# Reefing-Telemetry.net
KiCad netlist of a schematic drawn in Altium Designer
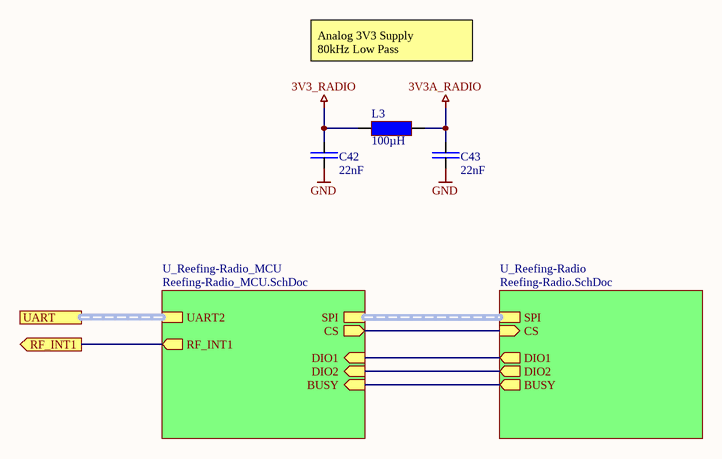
[diagram p0: Reefing-Telemetry.SchDoc]

(export (version "E")
  (design (tool "Eeschema 10.0.6"))
  (components
    (comp (ref "C42")
      (value "22nF")
      (footprint "SMD Keramikkondensator 0805")
      (description "SMD Ceramic Capacitor E6")
      (libsource (lib "Ceramic Capacitors-E6") (part "E6 - 22nF"))
    )
    (comp (ref "C43")
      (value "22nF")
      (footprint "SMD Keramikkondensator 0805")
      (description "SMD Ceramic Capacitor E6")
      (libsource (lib "Ceramic Capacitors-E6") (part "E6 - 22nF"))
    )
    (comp (ref "L3")
      (value "100µH")
      (footprint "SMD Inductor 1812")
      (description "0.25A 100µH ±20% 144mΩ SMD Power Inductors")
      (libsource (lib "Inductors") (part "Inductor 100µH / 0.25A"))
    )
  )
  (nets
    (net (code "8") (name "3V3A_RADIO") (class "Default")
      (node (ref "C43") (pin "2") (pinfunction "2_2") (pintype "passive"))
      (node (ref "L3") (pin "2") (pinfunction "2_2") (pintype "passive"))
    )
    (net (code "9") (name "3V3_RADIO") (class "Default")
      (node (ref "C42") (pin "2") (pinfunction "2_2") (pintype "passive"))
      (node (ref "L3") (pin "1") (pinfunction "1_1") (pintype "passive"))
    )
    (net (code "10") (name "GND") (class "Default")
      (node (ref "C42") (pin "1") (pinfunction "1_1") (pintype "passive"))
      (node (ref "C43") (pin "1") (pinfunction "1_1") (pintype "passive"))
    )
  )
)
